# Transmitter_Schematic.net
KiCad netlist of a schematic drawn in EAGLE
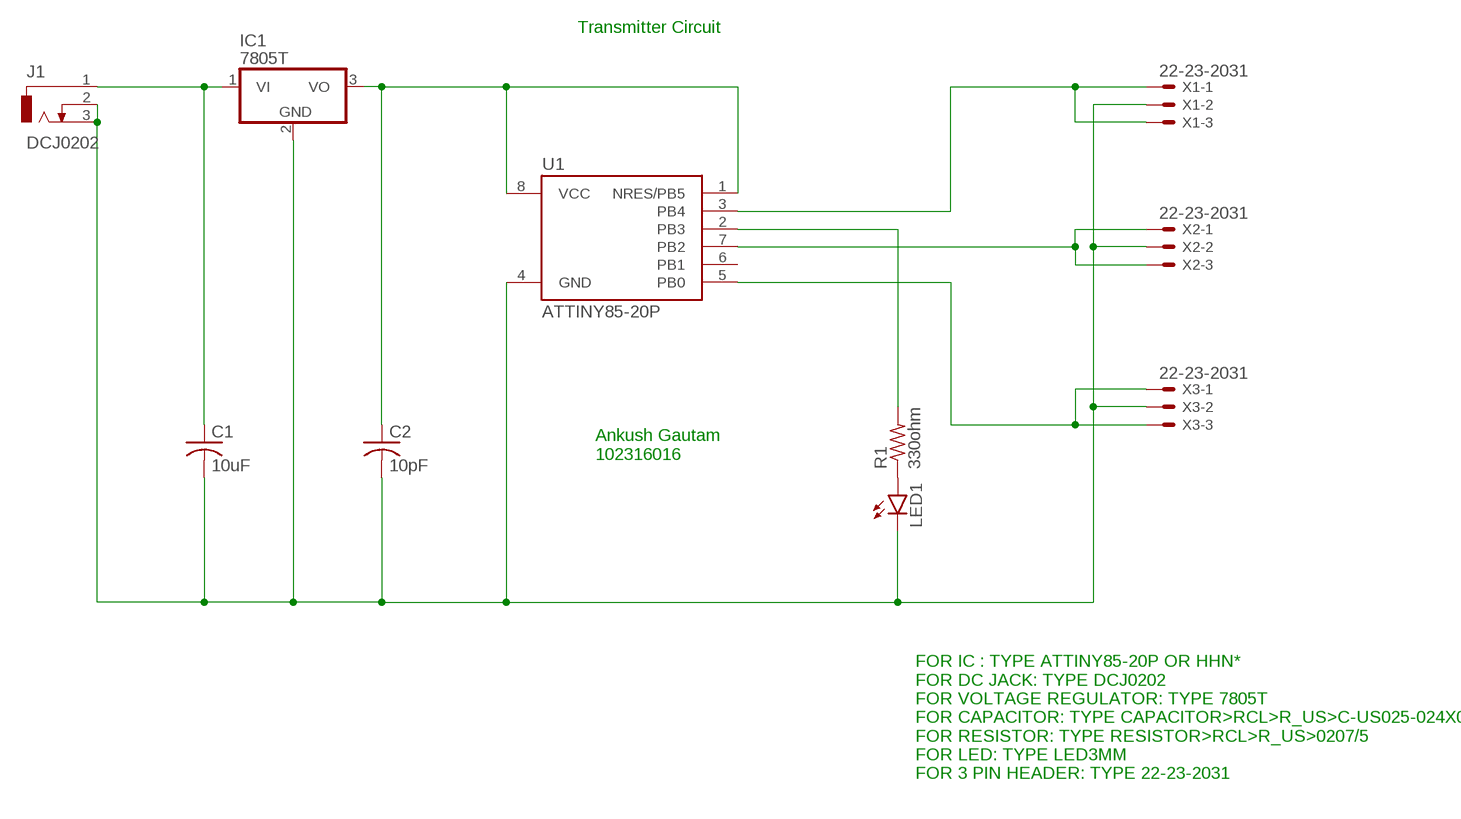
[diagram p0: schematic, sheet 1]

(export (version "E")
  (design (tool "Eeschema 10.0.6"))
  (components
    (comp (ref "C1")
      (value "10uF")
      (footprint "eagle-import:C025-024X044")
      (libsource (lib "eagle-import") (part "C-US025-024X044"))
    )
    (comp (ref "C2")
      (value "10pF")
      (footprint "eagle-import:C025-024X044")
      (libsource (lib "eagle-import") (part "C-US025-024X044"))
    )
    (comp (ref "IC1")
      (value "7805T")
      (footprint "eagle-import:TO220H")
      (libsource (lib "eagle-import") (part "78T05"))
    )
    (comp (ref "J1")
      (value "DCJ0202")
      (footprint "eagle-import:DCJ0202")
      (libsource (lib "eagle-import") (part "DCJ0202"))
    )
    (comp (ref "LED1")
      (value "LED3MM")
      (footprint "eagle-import:LED3MM")
      (libsource (lib "eagle-import") (part "LED3MM"))
    )
    (comp (ref "R1")
      (value "330ohm")
      (footprint "eagle-import:0204_5")
      (libsource (lib "eagle-import") (part "R-US_0204/5"))
    )
    (comp (ref "U1")
      (value "ATTINY85-20P")
      (footprint "eagle-import:PDIP08_300MIL")
      (libsource (lib "eagle-import") (part "ATTINY85P-20"))
    )
    (comp (ref "X1")
      (value "22-23-2031")
      (footprint "eagle-import:22-23-2031")
      (fields (field (name "MF") "MOLEX"))
      (libsource (lib "eagle-import") (part "22-23-2031"))
    )
    (comp (ref "X2")
      (value "22-23-2031")
      (footprint "eagle-import:22-23-2031")
      (fields (field (name "MF") "MOLEX"))
      (libsource (lib "eagle-import") (part "22-23-2031"))
    )
    (comp (ref "X3")
      (value "22-23-2031")
      (footprint "eagle-import:22-23-2031")
      (fields (field (name "MF") "MOLEX"))
      (libsource (lib "eagle-import") (part "22-23-2031"))
    )
  )
  (nets
    (net (code "1") (name "Net-(IC1-GND)") (class "Default")
      (node (ref "C1") (pin "2") (pinfunction "2_2") (pintype "passive"))
      (node (ref "C2") (pin "2") (pinfunction "2_2") (pintype "passive"))
      (node (ref "IC1") (pin "2") (pinfunction "GND_2") (pintype "passive"))
      (node (ref "J1") (pin "2") (pinfunction "2_2") (pintype "passive"))
      (node (ref "J1") (pin "3") (pinfunction "3_3") (pintype "passive"))
      (node (ref "LED1") (pin "K") (pinfunction "C_K") (pintype "passive"))
      (node (ref "U1") (pin "4") (pinfunction "GND_4") (pintype "power_in"))
      (node (ref "X1") (pin "2") (pinfunction "S_2") (pintype "passive"))
      (node (ref "X2") (pin "2") (pinfunction "S_2") (pintype "passive"))
      (node (ref "X3") (pin "2") (pinfunction "S_2") (pintype "passive"))
    )
    (net (code "2") (name "Net-(IC1-VI)") (class "Default")
      (node (ref "C1") (pin "1") (pinfunction "1_1") (pintype "passive"))
      (node (ref "IC1") (pin "1") (pinfunction "VI_1") (pintype "input"))
      (node (ref "J1") (pin "1") (pinfunction "1_1") (pintype "passive"))
    )
    (net (code "3") (name "Net-(IC1-VO)") (class "Default")
      (node (ref "C2") (pin "1") (pinfunction "1_1") (pintype "passive"))
      (node (ref "IC1") (pin "3") (pinfunction "VO_3") (pintype "passive"))
      (node (ref "U1") (pin "1") (pinfunction "NRES/PB5_1") (pintype "bidirectional"))
      (node (ref "U1") (pin "8") (pinfunction "VCC_8") (pintype "power_in"))
    )
    (net (code "4") (name "Net-(LED1-PadA)") (class "Default")
      (node (ref "LED1") (pin "A") (pinfunction "A_A") (pintype "passive"))
      (node (ref "R1") (pin "1") (pinfunction "1_1") (pintype "passive"))
    )
    (net (code "5") (name "Net-(U1-PB0)") (class "Default")
      (node (ref "U1") (pin "5") (pinfunction "PB0_5") (pintype "bidirectional"))
      (node (ref "X3") (pin "1") (pinfunction "S_1") (pintype "passive"))
      (node (ref "X3") (pin "3") (pinfunction "S_3") (pintype "passive"))
    )
    (net (code "6") (name "Net-(U1-PB2)") (class "Default")
      (node (ref "U1") (pin "7") (pinfunction "PB2_7") (pintype "bidirectional"))
      (node (ref "X2") (pin "1") (pinfunction "S_1") (pintype "passive"))
      (node (ref "X2") (pin "3") (pinfunction "S_3") (pintype "passive"))
    )
    (net (code "7") (name "Net-(U1-PB3)") (class "Default")
      (node (ref "R1") (pin "2") (pinfunction "2_2") (pintype "passive"))
      (node (ref "U1") (pin "2") (pinfunction "PB3_2") (pintype "bidirectional"))
    )
    (net (code "8") (name "Net-(U1-PB4)") (class "Default")
      (node (ref "U1") (pin "3") (pinfunction "PB4_3") (pintype "bidirectional"))
      (node (ref "X1") (pin "1") (pinfunction "S_1") (pintype "passive"))
      (node (ref "X1") (pin "3") (pinfunction "S_3") (pintype "passive"))
    )
    (net (code "9") (name "unconnected-(U1-PB1-Pad6)") (class "Default")
      (node (ref "U1") (pin "6") (pinfunction "PB1_6") (pintype "bidirectional"))
    )
  )
)
